# Sweep_Oscillator.net
KiCad netlist of a schematic drawn in Altium Designer
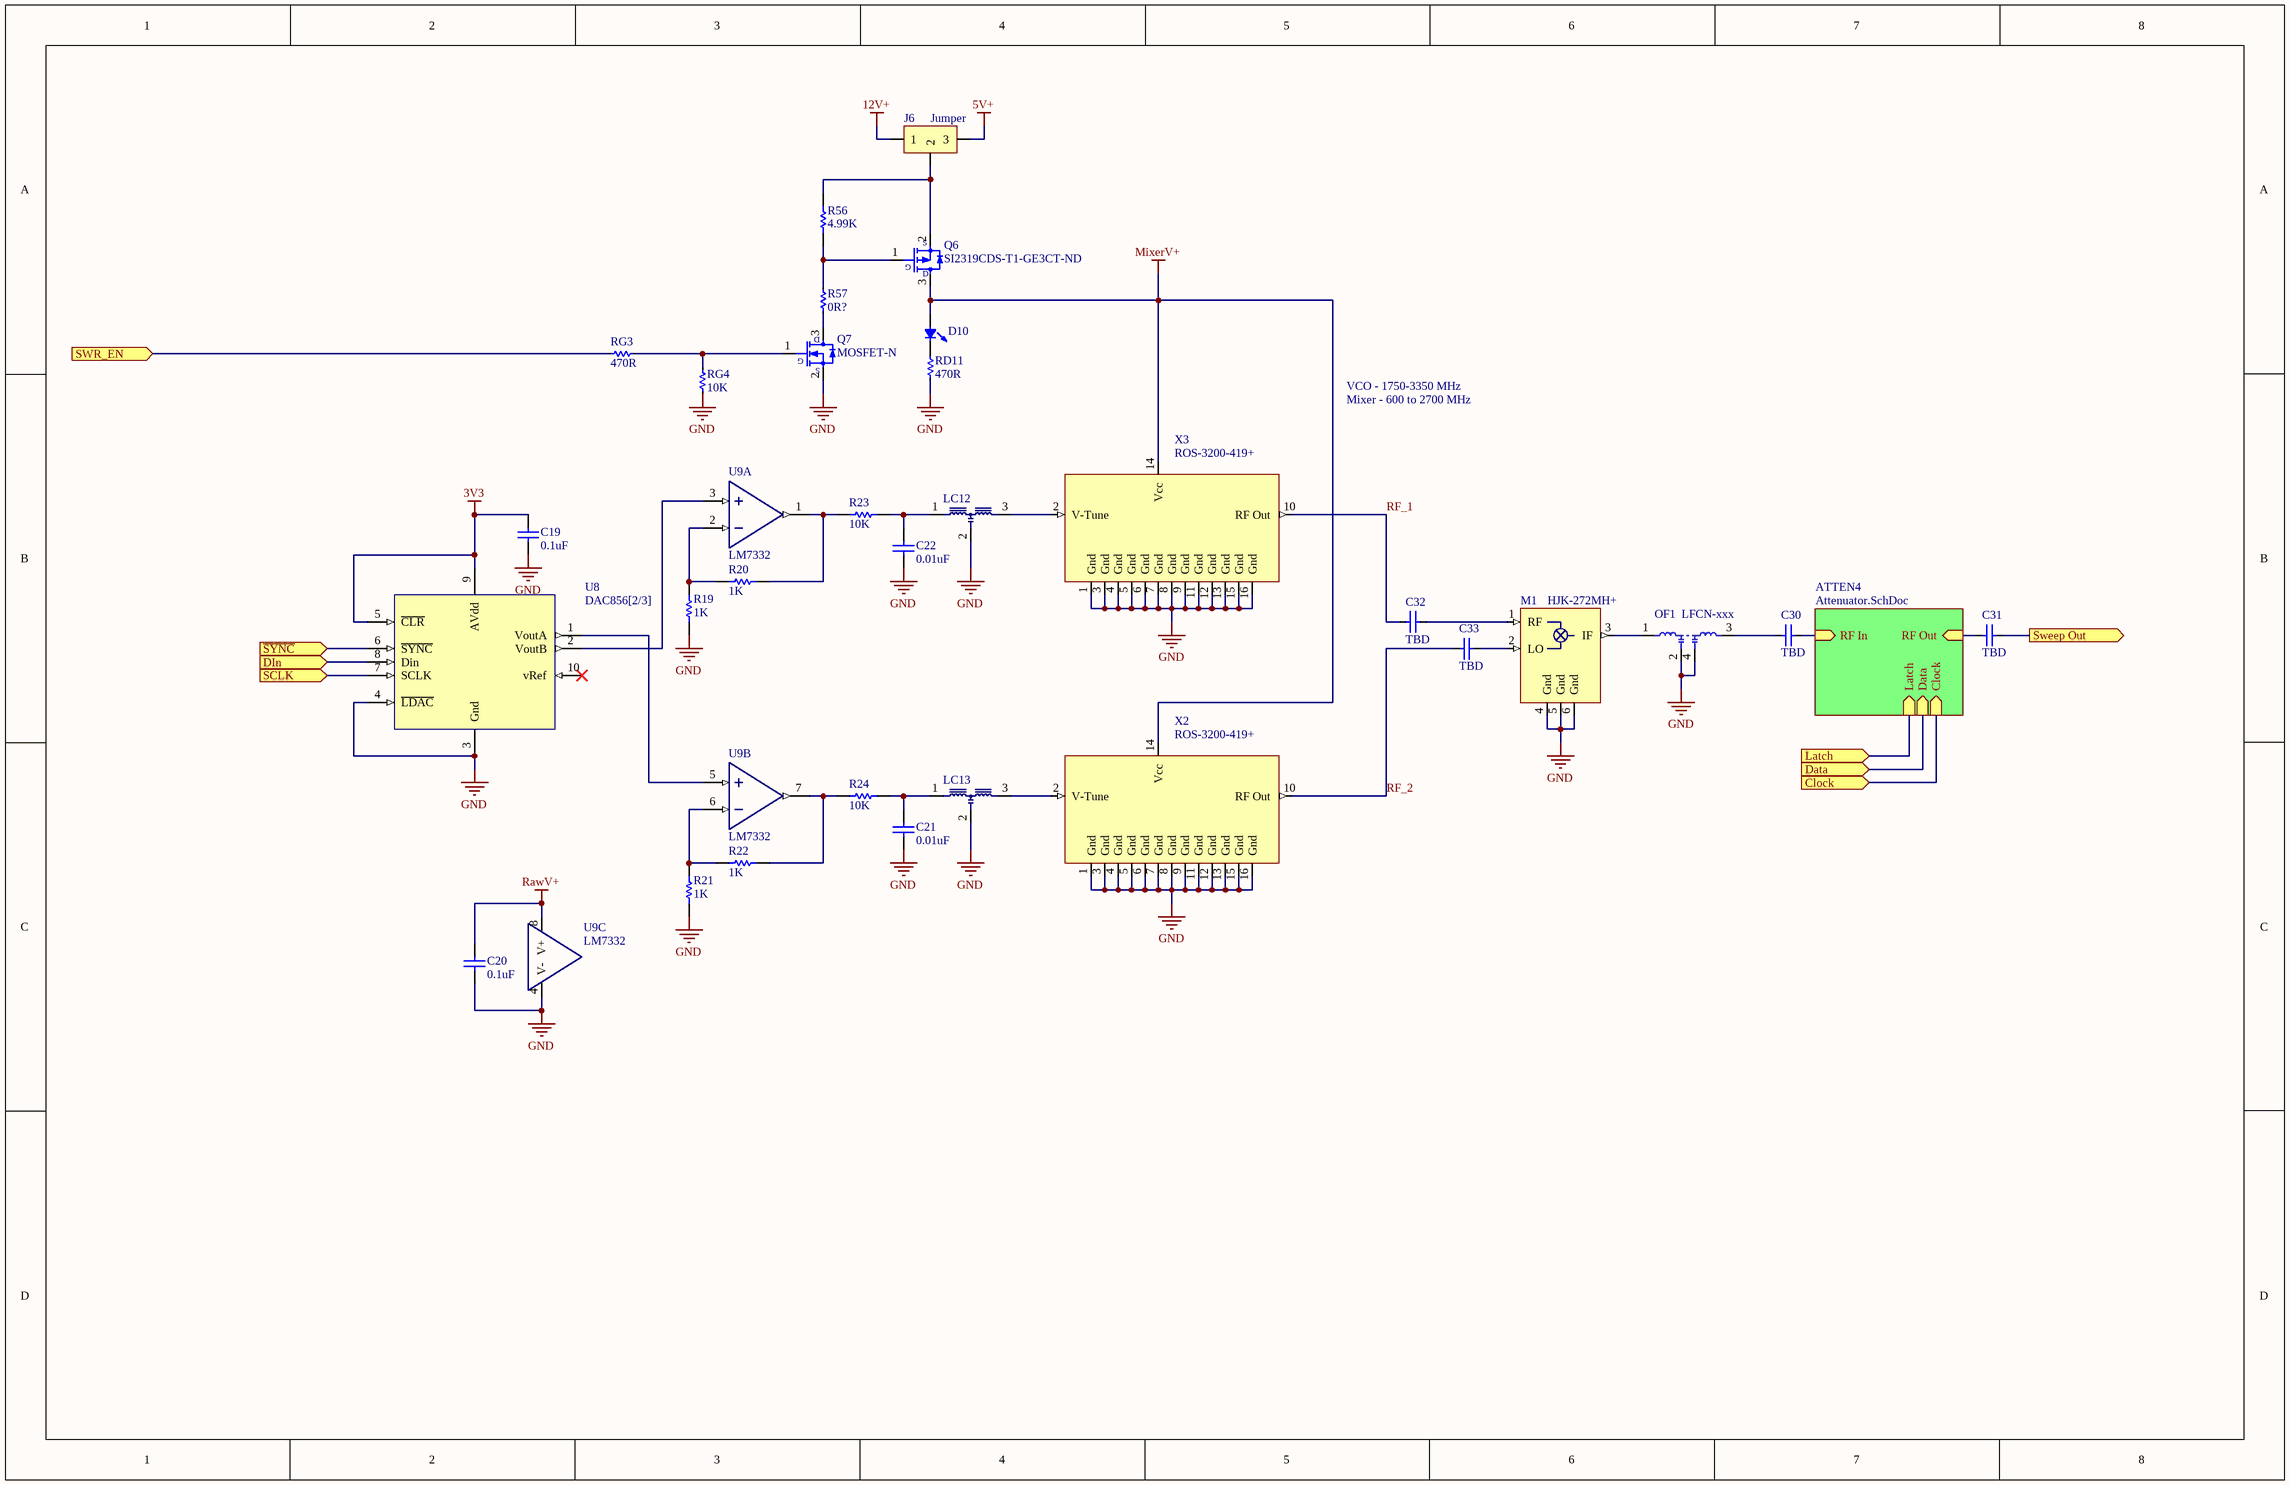
[diagram p0: Sweep Oscillator.SchDoc]

(export (version "E")
  (design (tool "Eeschema 10.0.6"))
  (components
    (comp (ref "C19")
      (value "0.1uF")
      (footprint "0603C")
      (description "Capacitor (Semiconductor SIM Model)")
      (fields (field (name "Comment") "Cap Semi") (field (name "PUBLISHER") "Altium Limited"))
      (libsource (lib "Miscellaneous Devices") (part "Cap Semi"))
    )
    (comp (ref "C20")
      (value "0.1uF")
      (footprint "0603C")
      (description "Capacitor (Semiconductor SIM Model)")
      (fields (field (name "Comment") "Cap Semi") (field (name "PUBLISHER") "Altium Limited"))
      (libsource (lib "Miscellaneous Devices") (part "Cap Semi"))
    )
    (comp (ref "C21")
      (value "0.01uF")
      (footprint "0603C")
      (description "Capacitor (Semiconductor SIM Model)")
      (fields (field (name "Comment") "Cap Semi") (field (name "PUBLISHER") "Altium Limited"))
      (libsource (lib "Miscellaneous Devices") (part "Cap Semi"))
    )
    (comp (ref "C22")
      (value "0.01uF")
      (footprint "0603C")
      (description "Capacitor (Semiconductor SIM Model)")
      (fields (field (name "Comment") "Cap Semi") (field (name "PUBLISHER") "Altium Limited"))
      (libsource (lib "Miscellaneous Devices") (part "Cap Semi"))
    )
    (comp (ref "C30")
      (value "TBD")
      (footprint "0402C")
      (description "Capacitor")
      (fields (field (name "Comment") "Cap") (field (name "PUBLISHER") "Altium Limited"))
      (libsource (lib "Miscellaneous Devices") (part "Cap"))
    )
    (comp (ref "C31")
      (value "TBD")
      (footprint "0402C")
      (description "Capacitor")
      (fields (field (name "Comment") "Cap") (field (name "PUBLISHER") "Altium Limited"))
      (libsource (lib "Miscellaneous Devices") (part "Cap"))
    )
    (comp (ref "C32")
      (value "TBD")
      (footprint "0402C")
      (description "Capacitor")
      (fields (field (name "Comment") "Cap") (field (name "PUBLISHER") "Altium Limited"))
      (libsource (lib "Miscellaneous Devices") (part "Cap"))
    )
    (comp (ref "C33")
      (value "TBD")
      (footprint "0402C")
      (description "Capacitor")
      (fields (field (name "Comment") "Cap") (field (name "PUBLISHER") "Altium Limited"))
      (libsource (lib "Miscellaneous Devices") (part "Cap"))
    )
    (comp (ref "D10")
      (value "LED0")
      (footprint "0603 SMT LED")
      (description "T 1 3/4 LED")
      (fields (field (name "PUBLISHER") "Altium Limited"))
      (libsource (lib "Miscellaneous Devices") (part "LED0"))
    )
    (comp (ref "J6")
      (value "Jumper")
      (footprint "HDR1X3")
      (description "Jumper - 3-Pin")
      (fields (field (name "PUBLISHER") "Altium Limited"))
      (libsource (lib "Miscellaneous Connectors") (part "Jumper - 3 Pin"))
    )
    (comp (ref "LC12")
      (value "MEM2012F")
      (footprint "MEM2012S LC Filter")
      (description "Signal Line 3-terminal Filters")
      (libsource (lib "Unsorted") (part "MEM2012F - Signal Filter"))
    )
    (comp (ref "LC13")
      (value "MEM2012F")
      (footprint "MEM2012S LC Filter")
      (description "Signal Line 3-terminal Filters")
      (libsource (lib "Unsorted") (part "MEM2012F - Signal Filter"))
    )
    (comp (ref "M1")
      (value "HJK-272MH+")
      (footprint "TTT881")
      (description "Wideband Frequency Mixer Level 13 (LO Power +13 dBm) 600 to 2700 MHz")
      (libsource (lib "RF Components") (part "HJK-272MH+"))
    )
    (comp (ref "OF1")
      (value "LFCN-xxx")
      (footprint "FV1206")
      (description "Ceramic Low Pass Filter")
      (libsource (lib "RF Components") (part "LFCN-xxx Filter"))
    )
    (comp (ref "Q6")
      (value "SI2319CDS-T1-GE3CT-ND")
      (footprint "SOT23-3N")
      (description "P-Channel MOSFET")
      (fields (field (name "PUBLISHER") "Altium Limited"))
      (libsource (lib "Miscellaneous Devices") (part "MOSFET-P"))
    )
    (comp (ref "Q7")
      (value "MOSFET-N")
      (footprint "SOT23-3N")
      (description "N-Channel MOSFET")
      (fields (field (name "PUBLISHER") "Altium Limited"))
      (libsource (lib "Miscellaneous Devices") (part "MOSFET-N"))
    )
    (comp (ref "R19")
      (value "1K")
      (footprint "0603R")
      (description "Semiconductor Resistor")
      (fields (field (name "Comment") "Res Semi") (field (name "PUBLISHER") "Altium Limited"))
      (libsource (lib "Miscellaneous Devices") (part "Res Semi"))
    )
    (comp (ref "R20")
      (value "1K")
      (footprint "0603R")
      (description "Semiconductor Resistor")
      (fields (field (name "Comment") "Res Semi") (field (name "PUBLISHER") "Altium Limited"))
      (libsource (lib "Miscellaneous Devices") (part "Res Semi"))
    )
    (comp (ref "R21")
      (value "1K")
      (footprint "0603R")
      (description "Semiconductor Resistor")
      (fields (field (name "Comment") "Res Semi") (field (name "PUBLISHER") "Altium Limited"))
      (libsource (lib "Miscellaneous Devices") (part "Res Semi"))
    )
    (comp (ref "R22")
      (value "1K")
      (footprint "0603R")
      (description "Semiconductor Resistor")
      (fields (field (name "Comment") "Res Semi") (field (name "PUBLISHER") "Altium Limited"))
      (libsource (lib "Miscellaneous Devices") (part "Res Semi"))
    )
    (comp (ref "R23")
      (value "10K")
      (footprint "0603R")
      (description "Semiconductor Resistor")
      (fields (field (name "Comment") "Res Semi") (field (name "PUBLISHER") "Altium Limited"))
      (libsource (lib "Miscellaneous Devices") (part "Res Semi"))
    )
    (comp (ref "R24")
      (value "10K")
      (footprint "0603R")
      (description "Semiconductor Resistor")
      (fields (field (name "Comment") "Res Semi") (field (name "PUBLISHER") "Altium Limited"))
      (libsource (lib "Miscellaneous Devices") (part "Res Semi"))
    )
    (comp (ref "R56")
      (value "4.99K")
      (footprint "0603R")
      (description "Semiconductor Resistor")
      (fields (field (name "Comment") "Res Semi") (field (name "PUBLISHER") "Altium Limited"))
      (libsource (lib "Miscellaneous Devices") (part "Res Semi"))
    )
    (comp (ref "R57")
      (value "0R?")
      (footprint "0603R")
      (description "Semiconductor Resistor")
      (fields (field (name "Comment") "Res Semi Small") (field (name "PUBLISHER") "Altium Limited"))
      (libsource (lib "Miscellaneous Devices") (part "Res Semi Small"))
    )
    (comp (ref "RD11")
      (value "470R")
      (footprint "0603R")
      (description "Semiconductor Resistor")
      (fields (field (name "Comment") "Res Semi Small") (field (name "PUBLISHER") "Altium Limited"))
      (libsource (lib "Miscellaneous Devices") (part "Res Semi Small"))
    )
    (comp (ref "RG3")
      (value "470R")
      (footprint "0603R")
      (description "Semiconductor Resistor")
      (fields (field (name "Comment") "Res Semi Small") (field (name "PUBLISHER") "Altium Limited"))
      (libsource (lib "Miscellaneous Devices") (part "Res Semi Small"))
    )
    (comp (ref "RG4")
      (value "10K")
      (footprint "0603R")
      (description "Semiconductor Resistor")
      (fields (field (name "Comment") "Res Semi Small") (field (name "PUBLISHER") "Altium Limited"))
      (libsource (lib "Miscellaneous Devices") (part "Res Semi Small"))
    )
    (comp (ref "U8")
      (value "DAC856[2/3]")
      (footprint "TSSOP50P490-10AN")
      (libsource (lib "ICs") (part "DAC856[2/3]"))
    )
    (comp (ref "U9")
      (value "LM7332")
      (footprint "SOIC127P600-8CN")
      (description "Dual Rail-to-Rail Input/Output, 30V, Wide Voltage Range, High Output Operational Amplifier")
      (libsource (lib "ICs") (part "LM7332"))
    )
    (comp (ref "X2")
      (value "ROS-3200-419+")
      (footprint "CK605")
      (description "Linear Tuning 2165 to 2650 MHz SMT Voltage Controlled Oscillator")
      (libsource (lib "RF Components") (part "ROS-2650 VCO"))
    )
    (comp (ref "X3")
      (value "ROS-3200-419+")
      (footprint "CK605")
      (description "Linear Tuning 2165 to 2650 MHz SMT Voltage Controlled Oscillator")
      (libsource (lib "RF Components") (part "ROS-2650 VCO"))
    )
  )
  (nets
    (net (code "2") (name "/DIn") (class "Default")
      (node (ref "U8") (pin "8") (pinfunction "Din_8") (pintype "input"))
    )
    (net (code "5") (name "/RF In") (class "Default")
      (node (ref "C30") (pin "2") (pinfunction "2_2") (pintype "passive"))
    )
    (net (code "6") (name "/RF Out") (class "Default")
      (node (ref "C31") (pin "1") (pinfunction "1_1") (pintype "passive"))
    )
    (net (code "7") (name "/RF_1") (class "Default")
      (node (ref "C32") (pin "1") (pinfunction "1_1") (pintype "passive"))
      (node (ref "X3") (pin "10") (pinfunction "RF_Out_10") (pintype "output"))
    )
    (net (code "8") (name "/RF_2") (class "Default")
      (node (ref "C33") (pin "1") (pinfunction "1_1") (pintype "passive"))
      (node (ref "X2") (pin "10") (pinfunction "RF_Out_10") (pintype "output"))
    )
    (net (code "9") (name "/SCLK") (class "Default")
      (node (ref "U8") (pin "7") (pinfunction "SCLK_7") (pintype "input"))
    )
    (net (code "10") (name "/SWR_EN") (class "Default")
      (node (ref "RG3") (pin "1") (pinfunction "1_1") (pintype "passive"))
    )
    (net (code "11") (name "/SYNC") (class "Default")
      (node (ref "U8") (pin "6") (pinfunction "SYNC_6") (pintype "input"))
    )
    (net (code "12") (name "/Sweep Out") (class "Default")
      (node (ref "C31") (pin "2") (pinfunction "2_2") (pintype "passive"))
    )
    (net (code "13") (name "3V3") (class "Default")
      (node (ref "C19") (pin "2") (pinfunction "2_2") (pintype "passive"))
      (node (ref "U8") (pin "5") (pinfunction "CLR_5") (pintype "input"))
      (node (ref "U8") (pin "9") (pinfunction "AVdd_9") (pintype "power_in"))
    )
    (net (code "14") (name "5V+") (class "Default")
      (node (ref "J6") (pin "3") (pinfunction "3_3") (pintype "passive"))
    )
    (net (code "15") (name "12V+") (class "Default")
      (node (ref "J6") (pin "1") (pinfunction "1_1") (pintype "passive"))
    )
    (net (code "16") (name "GND") (class "Default")
      (node (ref "C19") (pin "1") (pinfunction "1_1") (pintype "passive"))
      (node (ref "C20") (pin "1") (pinfunction "1_1") (pintype "passive"))
      (node (ref "C21") (pin "1") (pinfunction "1_1") (pintype "passive"))
      (node (ref "C22") (pin "1") (pinfunction "1_1") (pintype "passive"))
      (node (ref "LC12") (pin "2") (pinfunction "2_2") (pintype "passive"))
      (node (ref "LC13") (pin "2") (pinfunction "2_2") (pintype "passive"))
      (node (ref "M1") (pin "4") (pinfunction "Gnd_4") (pintype "power_in"))
      (node (ref "M1") (pin "5") (pinfunction "Gnd_5") (pintype "power_in"))
      (node (ref "M1") (pin "6") (pinfunction "Gnd_6") (pintype "power_in"))
      (node (ref "OF1") (pin "2") (pintype "passive"))
      (node (ref "OF1") (pin "4") (pintype "passive"))
      (node (ref "Q7") (pin "2") (pinfunction "S_2") (pintype "passive"))
      (node (ref "R19") (pin "2") (pinfunction "2_2") (pintype "passive"))
      (node (ref "R21") (pin "1") (pinfunction "1_1") (pintype "passive"))
      (node (ref "RD11") (pin "2") (pinfunction "2_2") (pintype "passive"))
      (node (ref "RG4") (pin "1") (pinfunction "1_1") (pintype "passive"))
      (node (ref "U8") (pin "3") (pinfunction "Gnd_3") (pintype "power_in"))
      (node (ref "U8") (pin "4") (pinfunction "LDAC_4") (pintype "input"))
      (node (ref "U9") (pin "4") (pinfunction "V-_4") (pintype "power_in"))
      (node (ref "X2") (pin "1") (pinfunction "Gnd_1") (pintype "power_in"))
      (node (ref "X2") (pin "11") (pinfunction "Gnd_11") (pintype "power_in"))
      (node (ref "X2") (pin "12") (pinfunction "Gnd_12") (pintype "power_in"))
      (node (ref "X2") (pin "13") (pinfunction "Gnd_13") (pintype "power_in"))
      (node (ref "X2") (pin "15") (pinfunction "Gnd_15") (pintype "power_in"))
      (node (ref "X2") (pin "16") (pinfunction "Gnd_16") (pintype "power_in"))
      (node (ref "X2") (pin "3") (pinfunction "Gnd_3") (pintype "power_in"))
      (node (ref "X2") (pin "4") (pinfunction "Gnd_4") (pintype "power_in"))
      (node (ref "X2") (pin "5") (pinfunction "Gnd_5") (pintype "power_in"))
      (node (ref "X2") (pin "6") (pinfunction "Gnd_6") (pintype "power_in"))
      (node (ref "X2") (pin "7") (pinfunction "Gnd_7") (pintype "power_in"))
      (node (ref "X2") (pin "8") (pinfunction "Gnd_8") (pintype "power_in"))
      (node (ref "X2") (pin "9") (pinfunction "Gnd_9") (pintype "power_in"))
      (node (ref "X3") (pin "1") (pinfunction "Gnd_1") (pintype "power_in"))
      (node (ref "X3") (pin "11") (pinfunction "Gnd_11") (pintype "power_in"))
      (node (ref "X3") (pin "12") (pinfunction "Gnd_12") (pintype "power_in"))
      (node (ref "X3") (pin "13") (pinfunction "Gnd_13") (pintype "power_in"))
      (node (ref "X3") (pin "15") (pinfunction "Gnd_15") (pintype "power_in"))
      (node (ref "X3") (pin "16") (pinfunction "Gnd_16") (pintype "power_in"))
      (node (ref "X3") (pin "3") (pinfunction "Gnd_3") (pintype "power_in"))
      (node (ref "X3") (pin "4") (pinfunction "Gnd_4") (pintype "power_in"))
      (node (ref "X3") (pin "5") (pinfunction "Gnd_5") (pintype "power_in"))
      (node (ref "X3") (pin "6") (pinfunction "Gnd_6") (pintype "power_in"))
      (node (ref "X3") (pin "7") (pinfunction "Gnd_7") (pintype "power_in"))
      (node (ref "X3") (pin "8") (pinfunction "Gnd_8") (pintype "power_in"))
      (node (ref "X3") (pin "9") (pinfunction "Gnd_9") (pintype "power_in"))
    )
    (net (code "17") (name "MixerV+") (class "Default")
      (node (ref "D10") (pin "1") (pinfunction "1_1") (pintype "passive"))
      (node (ref "Q6") (pin "3") (pinfunction "S_3") (pintype "passive"))
      (node (ref "X2") (pin "14") (pinfunction "Vcc_14") (pintype "power_in"))
      (node (ref "X3") (pin "14") (pinfunction "Vcc_14") (pintype "power_in"))
    )
    (net (code "18") (name "Net-(C21-Pad2)") (class "Default")
      (node (ref "C21") (pin "2") (pinfunction "2_2") (pintype "passive"))
      (node (ref "LC13") (pin "1") (pinfunction "1_1") (pintype "passive"))
      (node (ref "R24") (pin "1") (pinfunction "1_1") (pintype "passive"))
    )
    (net (code "19") (name "Net-(C22-Pad2)") (class "Default")
      (node (ref "C22") (pin "2") (pinfunction "2_2") (pintype "passive"))
      (node (ref "LC12") (pin "1") (pinfunction "1_1") (pintype "passive"))
      (node (ref "R23") (pin "1") (pinfunction "1_1") (pintype "passive"))
    )
    (net (code "20") (name "Net-(C30-Pad1)") (class "Default")
      (node (ref "C30") (pin "1") (pinfunction "1_1") (pintype "passive"))
      (node (ref "OF1") (pin "3") (pintype "passive"))
    )
    (net (code "21") (name "Net-(D10-Pad2)") (class "Default")
      (node (ref "D10") (pin "2") (pinfunction "2_2") (pintype "passive"))
      (node (ref "RD11") (pin "1") (pinfunction "1_1") (pintype "passive"))
    )
    (net (code "22") (name "Net-(M1-IF)") (class "Default")
      (node (ref "M1") (pin "3") (pinfunction "IF_3") (pintype "output"))
      (node (ref "OF1") (pin "1") (pintype "passive"))
    )
    (net (code "23") (name "Net-(M1-LO)") (class "Default")
      (node (ref "C33") (pin "2") (pinfunction "2_2") (pintype "passive"))
      (node (ref "M1") (pin "2") (pinfunction "LO_2") (pintype "input"))
    )
    (net (code "24") (name "Net-(M1-RF)") (class "Default")
      (node (ref "C32") (pin "2") (pinfunction "2_2") (pintype "passive"))
      (node (ref "M1") (pin "1") (pinfunction "RF_1") (pintype "input"))
    )
    (net (code "25") (name "Net-(Q6-D)") (class "Default")
      (node (ref "J6") (pin "2") (pinfunction "2_2") (pintype "passive"))
      (node (ref "Q6") (pin "2") (pinfunction "D_2") (pintype "passive"))
      (node (ref "R56") (pin "2") (pinfunction "2_2") (pintype "passive"))
    )
    (net (code "26") (name "Net-(Q6-G)") (class "Default")
      (node (ref "Q6") (pin "1") (pinfunction "G_1") (pintype "passive"))
      (node (ref "R56") (pin "1") (pinfunction "1_1") (pintype "passive"))
      (node (ref "R57") (pin "1") (pinfunction "1_1") (pintype "passive"))
    )
    (net (code "27") (name "Net-(Q7-D)") (class "Default")
      (node (ref "Q7") (pin "3") (pinfunction "D_3") (pintype "passive"))
      (node (ref "R57") (pin "2") (pinfunction "2_2") (pintype "passive"))
    )
    (net (code "28") (name "Net-(Q7-G)") (class "Default")
      (node (ref "Q7") (pin "1") (pinfunction "G_1") (pintype "passive"))
      (node (ref "RG3") (pin "2") (pinfunction "2_2") (pintype "passive"))
      (node (ref "RG4") (pin "2") (pinfunction "2_2") (pintype "passive"))
    )
    (net (code "29") (name "Net-(U8-VoutA)") (class "Default")
      (node (ref "U8") (pin "1") (pinfunction "VoutA_1") (pintype "output"))
      (node (ref "U9") (pin "5") (pinfunction "In_B_+_5") (pintype "input"))
    )
    (net (code "30") (name "Net-(U8-VoutB)") (class "Default")
      (node (ref "U8") (pin "2") (pinfunction "VoutB_2") (pintype "output"))
      (node (ref "U9") (pin "3") (pinfunction "In_A_+_3") (pintype "input"))
    )
    (net (code "31") (name "Net-(U9A-In_A_-)") (class "Default")
      (node (ref "R19") (pin "1") (pinfunction "1_1") (pintype "passive"))
      (node (ref "R20") (pin "1") (pinfunction "1_1") (pintype "passive"))
      (node (ref "U9") (pin "2") (pinfunction "In_A_-_2") (pintype "input"))
    )
    (net (code "32") (name "Net-(U9A-Out_A)") (class "Default")
      (node (ref "R20") (pin "2") (pinfunction "2_2") (pintype "passive"))
      (node (ref "R23") (pin "2") (pinfunction "2_2") (pintype "passive"))
      (node (ref "U9") (pin "1") (pinfunction "Out_A_1") (pintype "output"))
    )
    (net (code "33") (name "Net-(U9B-In_B_-)") (class "Default")
      (node (ref "R21") (pin "2") (pinfunction "2_2") (pintype "passive"))
      (node (ref "R22") (pin "2") (pinfunction "2_2") (pintype "passive"))
      (node (ref "U9") (pin "6") (pinfunction "In_B_-_6") (pintype "input"))
    )
    (net (code "34") (name "Net-(U9B-Out_B)") (class "Default")
      (node (ref "R22") (pin "1") (pinfunction "1_1") (pintype "passive"))
      (node (ref "R24") (pin "2") (pinfunction "2_2") (pintype "passive"))
      (node (ref "U9") (pin "7") (pinfunction "Out_B_7") (pintype "output"))
    )
    (net (code "35") (name "Net-(X2-V-Tune)") (class "Default")
      (node (ref "LC13") (pin "3") (pinfunction "3_3") (pintype "passive"))
      (node (ref "X2") (pin "2") (pinfunction "V-Tune_2") (pintype "input"))
    )
    (net (code "36") (name "Net-(X3-V-Tune)") (class "Default")
      (node (ref "LC12") (pin "3") (pinfunction "3_3") (pintype "passive"))
      (node (ref "X3") (pin "2") (pinfunction "V-Tune_2") (pintype "input"))
    )
    (net (code "37") (name "RawV+") (class "Default")
      (node (ref "C20") (pin "2") (pinfunction "2_2") (pintype "passive"))
      (node (ref "U9") (pin "8") (pinfunction "V+_8") (pintype "power_in"))
    )
    (net (code "38") (name "unconnected-(U8-vRef-Pad10)") (class "Default")
      (node (ref "U8") (pin "10") (pinfunction "vRef_10") (pintype "input+no_connect"))
    )
  )
)
